# PWM_Driver.net
KiCad netlist of a schematic drawn in Altium Designer
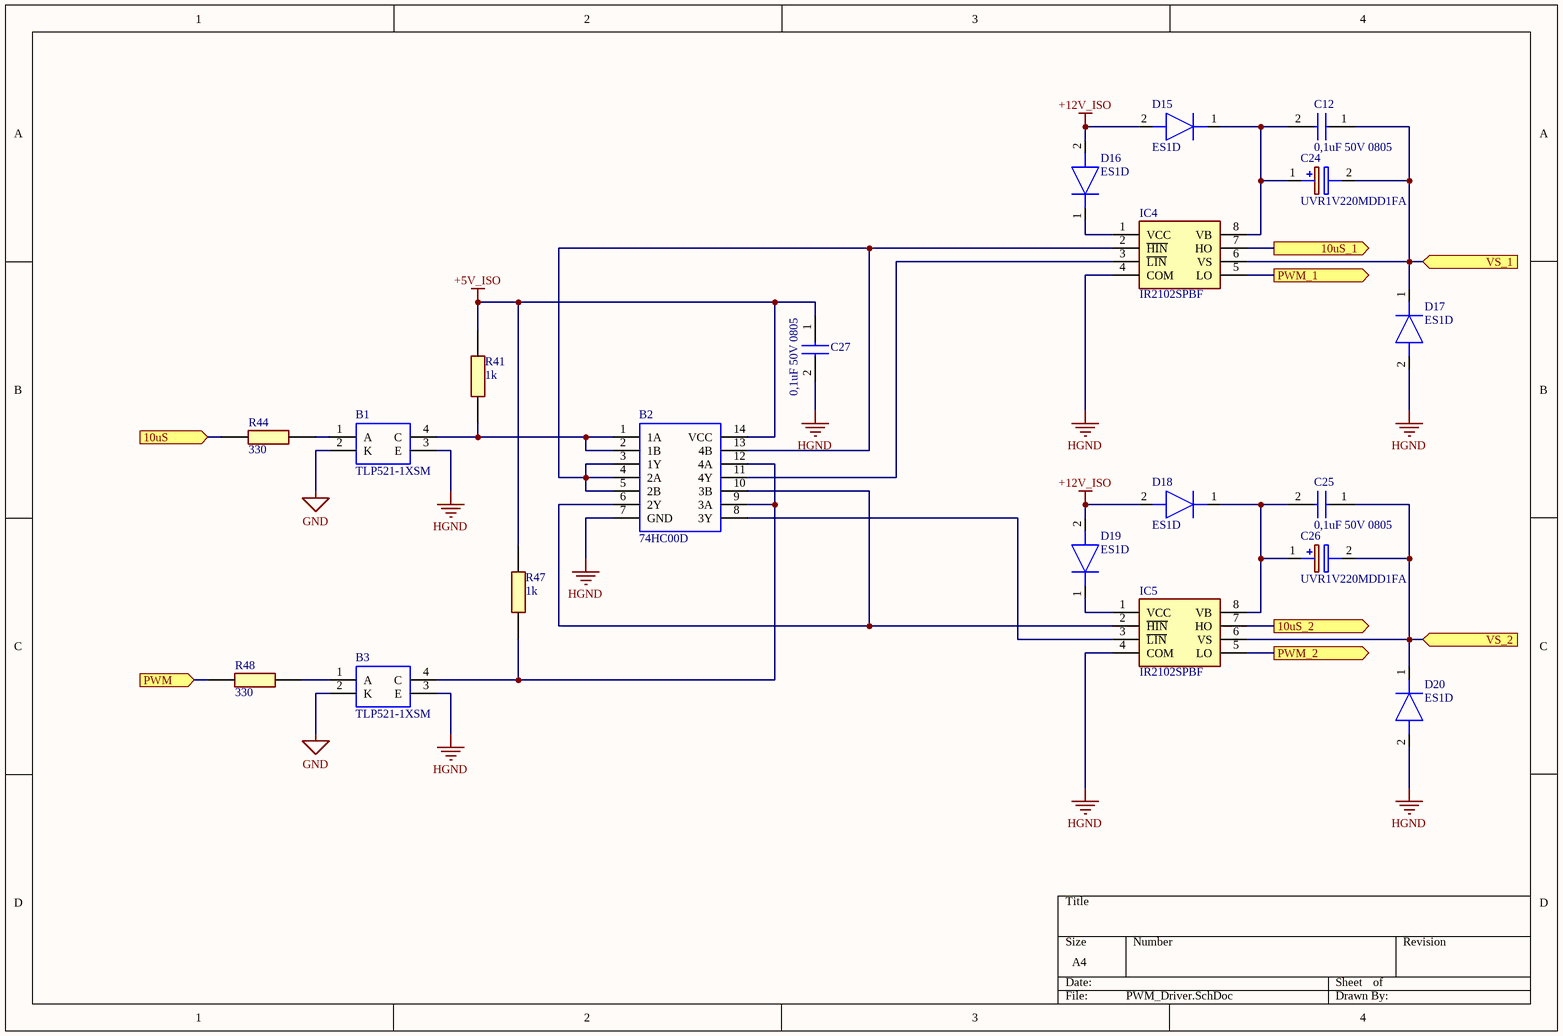
[diagram p0: PWM_Driver.SchDoc]

(export (version "E")
  (design (tool "Eeschema 10.0.6"))
  (components
    (comp (ref "B1")
      (value "TLP521-1XSM")
      (footprint "SOP254P1016X460-4N")
      (description "Optocoupler; SMD; Channels:1; Out: transistor; Uinsul:5.3kV")
      (libsource (lib "TLP521-1XSM") (part "TLP521-1XSM"))
    )
    (comp (ref "B2")
      (value "74HC00D")
      (footprint "SOIC127P600X175-14N")
      (description "NEXPERIA - 74HC00D - NAND Gate, 74HC00, 2 Input, 5.2 mA, 2 V to 6 V, SOIC-14")
      (fields (field (name "MOUSER PART NUMBER") "771-74HC00D"))
      (libsource (lib "74HC00D") (part "74HC00D"))
    )
    (comp (ref "B3")
      (value "TLP521-1XSM")
      (footprint "SOP254P1016X460-4N")
      (description "Optocoupler; SMD; Channels:1; Out: transistor; Uinsul:5.3kV")
      (libsource (lib "TLP521-1XSM") (part "TLP521-1XSM"))
    )
    (comp (ref "C12")
      (value "0,1uF 50V 0805")
      (footprint "SamacSys:CAPC2012X90N")
      (description "Capacitor")
      (libsource (lib "*") (part "MCMT21N470F250CT"))
    )
    (comp (ref "C24")
      (value "UVR1V220MDD1FA")
      (footprint "CAPPRD200W50D525H1250")
      (description "Capacitor Polarised")
      (fields (field (name "MOUSER PART NUMBER") "647-UVR1V220MDD1FA"))
      (libsource (lib "SamacSys") (part "UVR1V220MDD1FA"))
    )
    (comp (ref "C25")
      (value "0,1uF 50V 0805")
      (footprint "SamacSys:CAPC2012X90N")
      (description "Capacitor")
      (libsource (lib "*") (part "MCMT21N470F250CT"))
    )
    (comp (ref "C26")
      (value "UVR1V220MDD1FA")
      (footprint "CAPPRD200W50D525H1250")
      (description "Capacitor Polarised")
      (fields (field (name "MOUSER PART NUMBER") "647-UVR1V220MDD1FA"))
      (libsource (lib "SamacSys") (part "UVR1V220MDD1FA"))
    )
    (comp (ref "C27")
      (value "0,1uF 50V 0805")
      (footprint "SamacSys:CAPC2012X90N")
      (description "Capacitor")
      (libsource (lib "*") (part "MCMT21N470F250CT"))
    )
    (comp (ref "D15")
      (value "ES1D")
      (footprint "SamacSys:DIOM5226X295N")
      (description "Diode")
      (libsource (lib "SamacSys") (part "ES1D"))
    )
    (comp (ref "D16")
      (value "ES1D")
      (footprint "SamacSys:DIOM5226X295N")
      (description "Diode")
      (libsource (lib "SamacSys") (part "ES1D"))
    )
    (comp (ref "D17")
      (value "ES1D")
      (footprint "SamacSys:DIOM5226X295N")
      (description "Diode")
      (libsource (lib "SamacSys") (part "ES1D"))
    )
    (comp (ref "D18")
      (value "ES1D")
      (footprint "SamacSys:DIOM5226X295N")
      (description "Diode")
      (libsource (lib "SamacSys") (part "ES1D"))
    )
    (comp (ref "D19")
      (value "ES1D")
      (footprint "SamacSys:DIOM5226X295N")
      (description "Diode")
      (libsource (lib "SamacSys") (part "ES1D"))
    )
    (comp (ref "D20")
      (value "ES1D")
      (footprint "SamacSys:DIOM5226X295N")
      (description "Diode")
      (libsource (lib "SamacSys") (part "ES1D"))
    )
    (comp (ref "IC4")
      (value "IR2102SPBF")
      (footprint "SamacSys:SOIC127P600X175-8N")
      (description "Integrated Circuit")
      (fields (field (name "MOUSER PART NUMBER") "942-IR2102SPBF"))
      (libsource (lib "*") (part "IR2102SPBF"))
    )
    (comp (ref "IC5")
      (value "IR2102SPBF")
      (footprint "SamacSys:SOIC127P600X175-8N")
      (description "Integrated Circuit")
      (fields (field (name "MOUSER PART NUMBER") "942-IR2102SPBF"))
      (libsource (lib "*") (part "IR2102SPBF"))
    )
    (comp (ref "R41")
      (value "1k")
      (footprint "RESC2013X65N")
      (description "Resistor")
      (libsource (lib "") (part "ERJP06J822V_1"))
    )
    (comp (ref "R44")
      (value "330")
      (footprint "RESC2013X65N")
      (description "Resistor")
      (libsource (lib "SamacSys") (part "ERJP06J822V"))
    )
    (comp (ref "R47")
      (value "1k")
      (footprint "RESC2013X65N")
      (description "Resistor")
      (libsource (lib "") (part "ERJP06J822V_1"))
    )
    (comp (ref "R48")
      (value "330")
      (footprint "RESC2013X65N")
      (description "Resistor")
      (libsource (lib "SamacSys") (part "ERJP06J822V"))
    )
  )
  (nets
    (net (code "1") (name "+5V_ISO") (class "Default")
      (node (ref "B2") (pin "14") (pinfunction "VCC_14") (pintype "passive"))
      (node (ref "C27") (pin "1") (pinfunction "1_1") (pintype "passive"))
      (node (ref "R41") (pin "1") (pinfunction "1_1") (pintype "passive"))
      (node (ref "R47") (pin "1") (pinfunction "1_1") (pintype "passive"))
    )
    (net (code "2") (name "+12V_ISO") (class "Default")
      (node (ref "D15") (pin "2") (pinfunction "A_2") (pintype "passive"))
      (node (ref "D16") (pin "2") (pinfunction "A_2") (pintype "passive"))
      (node (ref "D18") (pin "2") (pinfunction "A_2") (pintype "passive"))
      (node (ref "D19") (pin "2") (pinfunction "A_2") (pintype "passive"))
    )
    (net (code "3") (name "/10uS") (class "Default")
      (node (ref "R44") (pin "1") (pinfunction "1_1") (pintype "passive"))
    )
    (net (code "4") (name "/10uS_1") (class "Default")
      (node (ref "IC4") (pin "7") (pinfunction "HO_7") (pintype "passive"))
    )
    (net (code "5") (name "/10uS_2") (class "Default")
      (node (ref "IC5") (pin "7") (pinfunction "HO_7") (pintype "passive"))
    )
    (net (code "6") (name "/PWM") (class "Default")
      (node (ref "R48") (pin "1") (pinfunction "1_1") (pintype "passive"))
    )
    (net (code "7") (name "/PWM_1") (class "Default")
      (node (ref "IC4") (pin "5") (pinfunction "LO_5") (pintype "passive"))
    )
    (net (code "8") (name "/PWM_2") (class "Default")
      (node (ref "IC5") (pin "5") (pinfunction "LO_5") (pintype "passive"))
    )
    (net (code "9") (name "/VS_1") (class "Default")
      (node (ref "C12") (pin "1") (pinfunction "1_1") (pintype "passive"))
      (node (ref "C24") (pin "2") (pinfunction "-_2") (pintype "passive"))
      (node (ref "D17") (pin "1") (pinfunction "K_1") (pintype "passive"))
      (node (ref "IC4") (pin "6") (pinfunction "VS_6") (pintype "passive"))
    )
    (net (code "10") (name "/VS_2") (class "Default")
      (node (ref "C25") (pin "1") (pinfunction "1_1") (pintype "passive"))
      (node (ref "C26") (pin "2") (pinfunction "-_2") (pintype "passive"))
      (node (ref "D20") (pin "1") (pinfunction "K_1") (pintype "passive"))
      (node (ref "IC5") (pin "6") (pinfunction "VS_6") (pintype "passive"))
    )
    (net (code "11") (name "GND") (class "Default")
      (node (ref "B1") (pin "2") (pinfunction "K_2") (pintype "passive"))
      (node (ref "B3") (pin "2") (pinfunction "K_2") (pintype "passive"))
    )
    (net (code "12") (name "HGND") (class "Default")
      (node (ref "B1") (pin "3") (pinfunction "E_3") (pintype "passive"))
      (node (ref "B2") (pin "7") (pinfunction "GND_7") (pintype "passive"))
      (node (ref "B3") (pin "3") (pinfunction "E_3") (pintype "passive"))
      (node (ref "C27") (pin "2") (pinfunction "2_2") (pintype "passive"))
      (node (ref "D17") (pin "2") (pinfunction "A_2") (pintype "passive"))
      (node (ref "D20") (pin "2") (pinfunction "A_2") (pintype "passive"))
      (node (ref "IC4") (pin "4") (pinfunction "COM_4") (pintype "passive"))
      (node (ref "IC5") (pin "4") (pinfunction "COM_4") (pintype "passive"))
    )
    (net (code "13") (name "Net-(B1-A)") (class "Default")
      (node (ref "B1") (pin "1") (pinfunction "A_1") (pintype "passive"))
      (node (ref "R44") (pin "2") (pinfunction "2_2") (pintype "passive"))
    )
    (net (code "14") (name "Net-(B1-C)") (class "Default")
      (node (ref "B1") (pin "4") (pinfunction "C_4") (pintype "passive"))
      (node (ref "B2") (pin "1") (pinfunction "1A_1") (pintype "passive"))
      (node (ref "B2") (pin "2") (pinfunction "1B_2") (pintype "passive"))
      (node (ref "R41") (pin "2") (pinfunction "2_2") (pintype "passive"))
    )
    (net (code "15") (name "Net-(B2-1Y)") (class "Default")
      (node (ref "B2") (pin "13") (pinfunction "4B_13") (pintype "passive"))
      (node (ref "B2") (pin "3") (pinfunction "1Y_3") (pintype "passive"))
      (node (ref "B2") (pin "4") (pinfunction "2A_4") (pintype "passive"))
      (node (ref "B2") (pin "5") (pinfunction "2B_5") (pintype "passive"))
      (node (ref "IC4") (pin "2") (pinfunction "~{HIN}_2") (pintype "passive"))
    )
    (net (code "16") (name "Net-(B2-2Y)") (class "Default")
      (node (ref "B2") (pin "10") (pinfunction "3B_10") (pintype "passive"))
      (node (ref "B2") (pin "6") (pinfunction "2Y_6") (pintype "passive"))
      (node (ref "IC5") (pin "2") (pinfunction "~{HIN}_2") (pintype "passive"))
    )
    (net (code "17") (name "Net-(B2-3A)") (class "Default")
      (node (ref "B2") (pin "12") (pinfunction "4A_12") (pintype "passive"))
      (node (ref "B2") (pin "9") (pinfunction "3A_9") (pintype "passive"))
      (node (ref "B3") (pin "4") (pinfunction "C_4") (pintype "passive"))
      (node (ref "R47") (pin "2") (pinfunction "2_2") (pintype "passive"))
    )
    (net (code "18") (name "Net-(B2-3Y)") (class "Default")
      (node (ref "B2") (pin "8") (pinfunction "3Y_8") (pintype "passive"))
      (node (ref "IC5") (pin "3") (pinfunction "~{LIN}_3") (pintype "passive"))
    )
    (net (code "19") (name "Net-(B2-4Y)") (class "Default")
      (node (ref "B2") (pin "11") (pinfunction "4Y_11") (pintype "passive"))
      (node (ref "IC4") (pin "3") (pinfunction "~{LIN}_3") (pintype "passive"))
    )
    (net (code "20") (name "Net-(B3-A)") (class "Default")
      (node (ref "B3") (pin "1") (pinfunction "A_1") (pintype "passive"))
      (node (ref "R48") (pin "2") (pinfunction "2_2") (pintype "passive"))
    )
    (net (code "21") (name "Net-(C24-+)") (class "Default")
      (node (ref "C12") (pin "2") (pinfunction "2_2") (pintype "passive"))
      (node (ref "C24") (pin "1") (pinfunction "+_1") (pintype "passive"))
      (node (ref "D15") (pin "1") (pinfunction "K_1") (pintype "passive"))
      (node (ref "IC4") (pin "8") (pinfunction "VB_8") (pintype "passive"))
    )
    (net (code "22") (name "Net-(C26-+)") (class "Default")
      (node (ref "C25") (pin "2") (pinfunction "2_2") (pintype "passive"))
      (node (ref "C26") (pin "1") (pinfunction "+_1") (pintype "passive"))
      (node (ref "D18") (pin "1") (pinfunction "K_1") (pintype "passive"))
      (node (ref "IC5") (pin "8") (pinfunction "VB_8") (pintype "passive"))
    )
    (net (code "23") (name "Net-(D16-K)") (class "Default")
      (node (ref "D16") (pin "1") (pinfunction "K_1") (pintype "passive"))
      (node (ref "IC4") (pin "1") (pinfunction "VCC_1") (pintype "passive"))
    )
    (net (code "24") (name "Net-(D19-K)") (class "Default")
      (node (ref "D19") (pin "1") (pinfunction "K_1") (pintype "passive"))
      (node (ref "IC5") (pin "1") (pinfunction "VCC_1") (pintype "passive"))
    )
  )
)
